# pisniffer.net
KiCad netlist of a schematic drawn in EAGLE
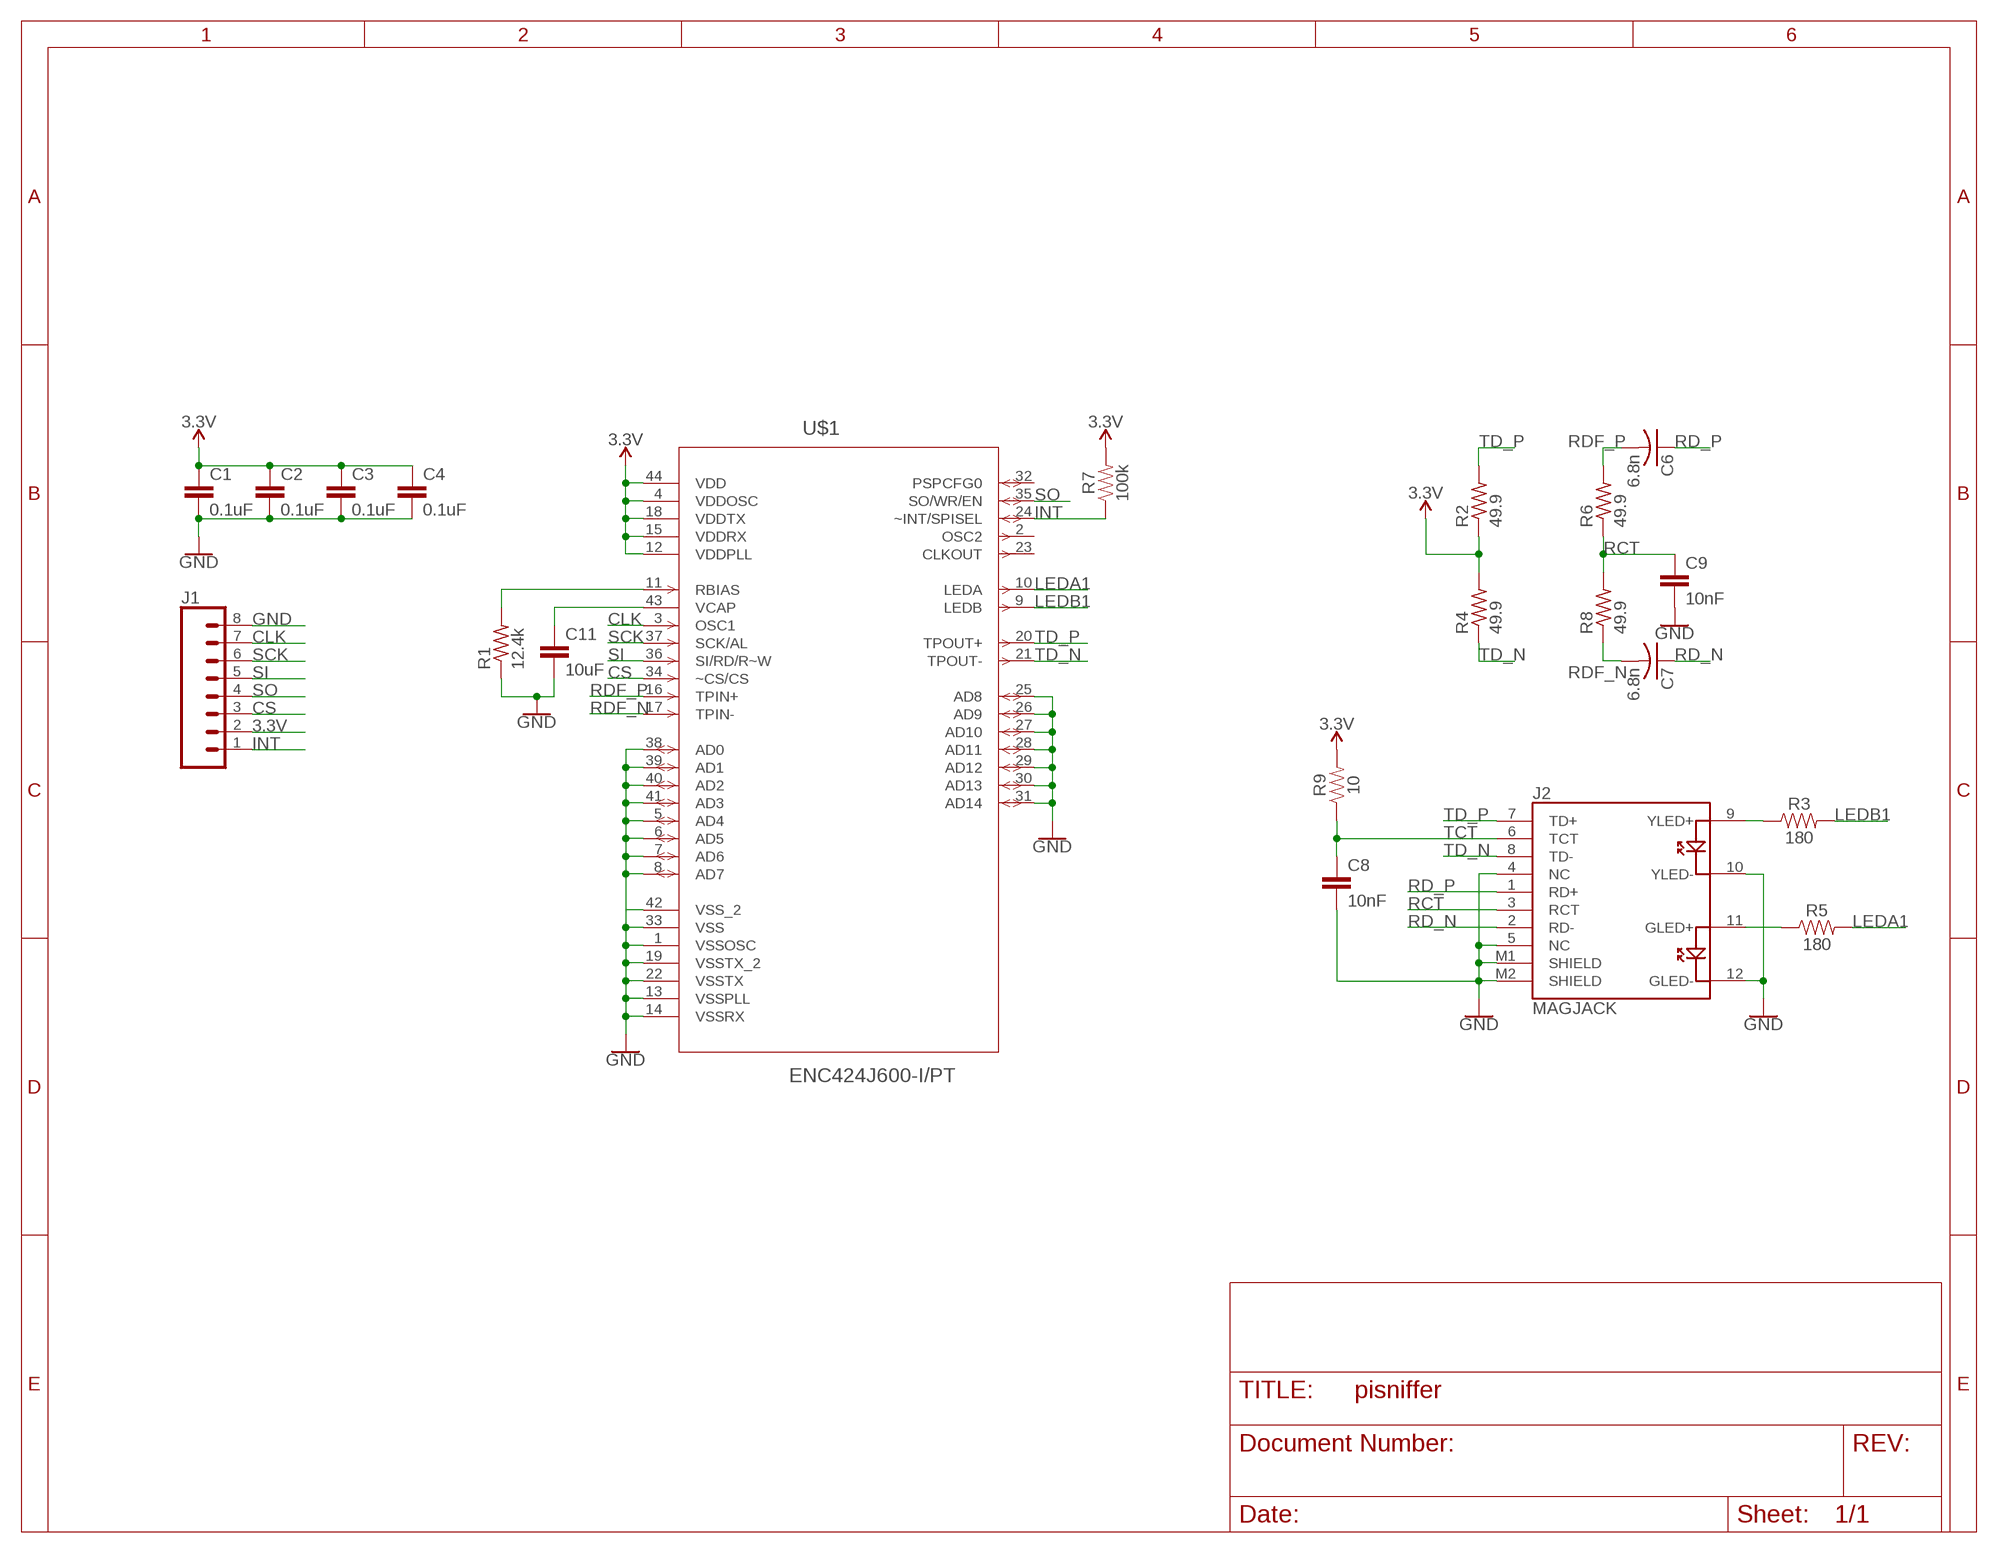
[diagram p0: schematic, sheet 1]

(export (version "E")
  (design (tool "Eeschema 10.0.6"))
  (components
    (comp (ref "C1")
      (value "0.1uF")
      (footprint "eagle-import:0603")
      (libsource (lib "eagle-import") (part "0.1UF-0603-25V-5%"))
    )
    (comp (ref "C2")
      (value "0.1uF")
      (footprint "eagle-import:0603")
      (libsource (lib "eagle-import") (part "0.1UF-0603-25V-5%"))
    )
    (comp (ref "C3")
      (value "0.1uF")
      (footprint "eagle-import:0603")
      (libsource (lib "eagle-import") (part "0.1UF-0603-25V-5%"))
    )
    (comp (ref "C4")
      (value "0.1uF")
      (footprint "eagle-import:0603")
      (libsource (lib "eagle-import") (part "0.1UF-0603-25V-5%"))
    )
    (comp (ref "C6")
      (value "6.8n")
      (footprint "eagle-import:C0603")
      (libsource (lib "eagle-import") (part "C-USC0603"))
    )
    (comp (ref "C7")
      (value "6.8n")
      (footprint "eagle-import:C0603")
      (libsource (lib "eagle-import") (part "C-USC0603"))
    )
    (comp (ref "C8")
      (value "10nF")
      (footprint "eagle-import:0603")
      (libsource (lib "eagle-import") (part "10NF-0603-50V-10%"))
    )
    (comp (ref "C9")
      (value "10nF")
      (footprint "eagle-import:0603")
      (libsource (lib "eagle-import") (part "10NF-0603-50V-10%"))
    )
    (comp (ref "C11")
      (value "10uF")
      (footprint "eagle-import:0603")
      (libsource (lib "eagle-import") (part "10UF-0603-6.3V-20%"))
    )
    (comp (ref "J1")
      (value "CONN_08\"")
      (footprint "eagle-import:1X08")
      (libsource (lib "eagle-import") (part "CONN_08{dblquote}"))
    )
    (comp (ref "J2")
      (value "MAGJACK")
      (footprint "eagle-import:MAGJACK")
      (libsource (lib "eagle-import") (part "MAGJACK"))
    )
    (comp (ref "R1")
      (value "12.4k")
      (footprint "eagle-import:R0603")
      (libsource (lib "eagle-import") (part "R-US_R0603"))
    )
    (comp (ref "R2")
      (value "49.9")
      (footprint "eagle-import:R0603")
      (libsource (lib "eagle-import") (part "R-US_R0603"))
    )
    (comp (ref "R3")
      (value "180")
      (footprint "eagle-import:0603")
      (libsource (lib "eagle-import") (part "180OHM-0603-1/10W-1%"))
    )
    (comp (ref "R4")
      (value "49.9")
      (footprint "eagle-import:R0603")
      (libsource (lib "eagle-import") (part "R-US_R0603"))
    )
    (comp (ref "R5")
      (value "180")
      (footprint "eagle-import:0603")
      (libsource (lib "eagle-import") (part "180OHM-0603-1/10W-1%"))
    )
    (comp (ref "R6")
      (value "49.9")
      (footprint "eagle-import:R0603")
      (libsource (lib "eagle-import") (part "R-US_R0603"))
    )
    (comp (ref "R7")
      (value "100k")
      (footprint "eagle-import:0603")
      (libsource (lib "eagle-import") (part "100KOHM-0603-1/10W-1%"))
    )
    (comp (ref "R8")
      (value "49.9")
      (footprint "eagle-import:R0603")
      (libsource (lib "eagle-import") (part "R-US_R0603"))
    )
    (comp (ref "R9")
      (value "10")
      (footprint "eagle-import:0603")
      (libsource (lib "eagle-import") (part "10OHM-0603-1/10W-1%"))
    )
    (comp (ref "U$1")
      (value "ENC424J600-I/PT")
      (footprint "eagle-import:QFP50P1200X1200X120-44N")
      (fields (field (name "MPN") "enc424j600-I/pt"))
      (libsource (lib "eagle-import") (part "ENC424J600-I/PT"))
    )
  )
  (nets
    (net (code "1") (name "/CLK") (class "Default")
      (node (ref "J1") (pin "7") (pinfunction "7_7") (pintype "passive"))
      (node (ref "U$1") (pin "3") (pinfunction "OSC1_3") (pintype "input"))
    )
    (net (code "2") (name "/CS") (class "Default")
      (node (ref "J1") (pin "3") (pinfunction "3_3") (pintype "passive"))
      (node (ref "U$1") (pin "34") (pinfunction "~{CS/CS}_34") (pintype "input"))
    )
    (net (code "3") (name "/INT") (class "Default")
      (node (ref "J1") (pin "1") (pinfunction "1_1") (pintype "passive"))
      (node (ref "R7") (pin "1") (pinfunction "1_1") (pintype "passive"))
      (node (ref "U$1") (pin "24") (pinfunction "~{INT/SPISEL}_24") (pintype "bidirectional"))
    )
    (net (code "4") (name "/LEDA1") (class "Default")
      (node (ref "R5") (pin "2") (pinfunction "2_2") (pintype "passive"))
      (node (ref "U$1") (pin "10") (pinfunction "LEDA_10") (pintype "output"))
    )
    (net (code "5") (name "/LEDB1") (class "Default")
      (node (ref "R3") (pin "2") (pinfunction "2_2") (pintype "passive"))
      (node (ref "U$1") (pin "9") (pinfunction "LEDB_9") (pintype "output"))
    )
    (net (code "6") (name "/RCT") (class "Default")
      (node (ref "C9") (pin "1") (pinfunction "1_1") (pintype "passive"))
      (node (ref "J2") (pin "3") (pinfunction "RCT_3") (pintype "bidirectional"))
      (node (ref "R6") (pin "1") (pinfunction "1_1") (pintype "passive"))
      (node (ref "R8") (pin "2") (pinfunction "2_2") (pintype "passive"))
    )
    (net (code "7") (name "/RDF_N") (class "Default")
      (node (ref "C7") (pin "2") (pinfunction "2_2") (pintype "passive"))
      (node (ref "R8") (pin "1") (pinfunction "1_1") (pintype "passive"))
      (node (ref "U$1") (pin "17") (pinfunction "TPIN-_17") (pintype "input"))
    )
    (net (code "8") (name "/RDF_P") (class "Default")
      (node (ref "C6") (pin "2") (pinfunction "2_2") (pintype "passive"))
      (node (ref "R6") (pin "2") (pinfunction "2_2") (pintype "passive"))
      (node (ref "U$1") (pin "16") (pinfunction "TPIN+_16") (pintype "input"))
    )
    (net (code "9") (name "/RD_N") (class "Default")
      (node (ref "C7") (pin "1") (pinfunction "1_1") (pintype "passive"))
      (node (ref "J2") (pin "2") (pinfunction "RD-_2") (pintype "bidirectional"))
    )
    (net (code "10") (name "/RD_P") (class "Default")
      (node (ref "C6") (pin "1") (pinfunction "1_1") (pintype "passive"))
      (node (ref "J2") (pin "1") (pinfunction "RD+_1") (pintype "bidirectional"))
    )
    (net (code "11") (name "/SCK") (class "Default")
      (node (ref "J1") (pin "6") (pinfunction "6_6") (pintype "passive"))
      (node (ref "U$1") (pin "37") (pinfunction "SCK/AL_37") (pintype "input"))
    )
    (net (code "12") (name "/SI") (class "Default")
      (node (ref "J1") (pin "5") (pinfunction "5_5") (pintype "passive"))
      (node (ref "U$1") (pin "36") (pinfunction "SI/RD/R~{W}_36") (pintype "input"))
    )
    (net (code "13") (name "/SO") (class "Default")
      (node (ref "J1") (pin "4") (pinfunction "4_4") (pintype "passive"))
      (node (ref "U$1") (pin "35") (pinfunction "SO/WR/EN_35") (pintype "bidirectional"))
    )
    (net (code "14") (name "/TCT") (class "Default")
      (node (ref "C8") (pin "1") (pinfunction "1_1") (pintype "passive"))
      (node (ref "J2") (pin "6") (pinfunction "TCT_6") (pintype "bidirectional"))
      (node (ref "R9") (pin "1") (pinfunction "1_1") (pintype "passive"))
    )
    (net (code "15") (name "/TD_N") (class "Default")
      (node (ref "J2") (pin "8") (pinfunction "TD-_8") (pintype "bidirectional"))
      (node (ref "R4") (pin "1") (pinfunction "1_1") (pintype "passive"))
      (node (ref "U$1") (pin "21") (pinfunction "TPOUT-_21") (pintype "output"))
    )
    (net (code "16") (name "/TD_P") (class "Default")
      (node (ref "J2") (pin "7") (pinfunction "TD+_7") (pintype "bidirectional"))
      (node (ref "R2") (pin "2") (pinfunction "2_2") (pintype "passive"))
      (node (ref "U$1") (pin "20") (pinfunction "TPOUT+_20") (pintype "output"))
    )
    (net (code "17") (name "3.3V") (class "Default")
      (node (ref "C1") (pin "1") (pinfunction "1_1") (pintype "passive"))
      (node (ref "C2") (pin "1") (pinfunction "1_1") (pintype "passive"))
      (node (ref "C3") (pin "1") (pinfunction "1_1") (pintype "passive"))
      (node (ref "C4") (pin "1") (pinfunction "1_1") (pintype "passive"))
      (node (ref "J1") (pin "2") (pinfunction "2_2") (pintype "passive"))
      (node (ref "R2") (pin "1") (pinfunction "1_1") (pintype "passive"))
      (node (ref "R4") (pin "2") (pinfunction "2_2") (pintype "passive"))
      (node (ref "R7") (pin "2") (pinfunction "2_2") (pintype "passive"))
      (node (ref "R9") (pin "2") (pinfunction "2_2") (pintype "passive"))
      (node (ref "U$1") (pin "12") (pinfunction "VDDPLL_12") (pintype "power_in"))
      (node (ref "U$1") (pin "15") (pinfunction "VDDRX_15") (pintype "power_in"))
      (node (ref "U$1") (pin "18") (pinfunction "VDDTX_18") (pintype "power_in"))
      (node (ref "U$1") (pin "4") (pinfunction "VDDOSC_4") (pintype "power_in"))
      (node (ref "U$1") (pin "44") (pinfunction "VDD_44") (pintype "power_in"))
    )
    (net (code "18") (name "GND") (class "Default")
      (node (ref "C1") (pin "2") (pinfunction "2_2") (pintype "passive"))
      (node (ref "C11") (pin "2") (pinfunction "2_2") (pintype "passive"))
      (node (ref "C2") (pin "2") (pinfunction "2_2") (pintype "passive"))
      (node (ref "C3") (pin "2") (pinfunction "2_2") (pintype "passive"))
      (node (ref "C4") (pin "2") (pinfunction "2_2") (pintype "passive"))
      (node (ref "C8") (pin "2") (pinfunction "2_2") (pintype "passive"))
      (node (ref "C9") (pin "2") (pinfunction "2_2") (pintype "passive"))
      (node (ref "J1") (pin "8") (pinfunction "8_8") (pintype "passive"))
      (node (ref "J2") (pin "10") (pinfunction "YLED-_10") (pintype "bidirectional"))
      (node (ref "J2") (pin "12") (pinfunction "GLED-_12") (pintype "bidirectional"))
      (node (ref "J2") (pin "4") (pinfunction "NC_4") (pintype "bidirectional"))
      (node (ref "J2") (pin "5") (pinfunction "NC_5") (pintype "bidirectional"))
      (node (ref "J2") (pin "M1") (pinfunction "SHIELD_M1") (pintype "bidirectional"))
      (node (ref "J2") (pin "M2") (pinfunction "SHIELD_M2") (pintype "bidirectional"))
      (node (ref "R1") (pin "1") (pinfunction "1_1") (pintype "passive"))
      (node (ref "U$1") (pin "1") (pinfunction "VSSOSC_1") (pintype "power_in"))
      (node (ref "U$1") (pin "13") (pinfunction "VSSPLL_13") (pintype "power_in"))
      (node (ref "U$1") (pin "14") (pinfunction "VSSRX_14") (pintype "power_in"))
      (node (ref "U$1") (pin "19") (pinfunction "VSSTX_2_19") (pintype "power_in"))
      (node (ref "U$1") (pin "22") (pinfunction "VSSTX_22") (pintype "power_in"))
      (node (ref "U$1") (pin "25") (pinfunction "AD8_25") (pintype "bidirectional"))
      (node (ref "U$1") (pin "26") (pinfunction "AD9_26") (pintype "bidirectional"))
      (node (ref "U$1") (pin "27") (pinfunction "AD10_27") (pintype "bidirectional"))
      (node (ref "U$1") (pin "28") (pinfunction "AD11_28") (pintype "bidirectional"))
      (node (ref "U$1") (pin "29") (pinfunction "AD12_29") (pintype "bidirectional"))
      (node (ref "U$1") (pin "30") (pinfunction "AD13_30") (pintype "bidirectional"))
      (node (ref "U$1") (pin "31") (pinfunction "AD14_31") (pintype "bidirectional"))
      (node (ref "U$1") (pin "33") (pinfunction "VSS_33") (pintype "power_in"))
      (node (ref "U$1") (pin "38") (pinfunction "AD0_38") (pintype "bidirectional"))
      (node (ref "U$1") (pin "39") (pinfunction "AD1_39") (pintype "bidirectional"))
      (node (ref "U$1") (pin "40") (pinfunction "AD2_40") (pintype "bidirectional"))
      (node (ref "U$1") (pin "41") (pinfunction "AD3_41") (pintype "bidirectional"))
      (node (ref "U$1") (pin "42") (pinfunction "VSS_2_42") (pintype "power_in"))
      (node (ref "U$1") (pin "5") (pinfunction "AD4_5") (pintype "bidirectional"))
      (node (ref "U$1") (pin "6") (pinfunction "AD5_6") (pintype "bidirectional"))
      (node (ref "U$1") (pin "7") (pinfunction "AD6_7") (pintype "bidirectional"))
      (node (ref "U$1") (pin "8") (pinfunction "AD7_8") (pintype "bidirectional"))
    )
    (net (code "19") (name "Net-(J2-GLED+)") (class "Default")
      (node (ref "J2") (pin "11") (pinfunction "GLED+_11") (pintype "bidirectional"))
      (node (ref "R5") (pin "1") (pinfunction "1_1") (pintype "passive"))
    )
    (net (code "20") (name "Net-(J2-YLED+)") (class "Default")
      (node (ref "J2") (pin "9") (pinfunction "YLED+_9") (pintype "bidirectional"))
      (node (ref "R3") (pin "1") (pinfunction "1_1") (pintype "passive"))
    )
    (net (code "21") (name "Net-(U$1-RBIAS)") (class "Default")
      (node (ref "R1") (pin "2") (pinfunction "2_2") (pintype "passive"))
      (node (ref "U$1") (pin "11") (pinfunction "RBIAS_11") (pintype "input"))
    )
    (net (code "22") (name "Net-(U$1-VCAP)") (class "Default")
      (node (ref "C11") (pin "1") (pinfunction "1_1") (pintype "passive"))
      (node (ref "U$1") (pin "43") (pinfunction "VCAP_43") (pintype "power_in"))
    )
    (net (code "23") (name "unconnected-(U$1-CLKOUT-Pad23)") (class "Default")
      (node (ref "U$1") (pin "23") (pinfunction "CLKOUT_23") (pintype "output"))
    )
    (net (code "24") (name "unconnected-(U$1-OSC2-Pad2)") (class "Default")
      (node (ref "U$1") (pin "2") (pinfunction "OSC2_2") (pintype "output"))
    )
    (net (code "25") (name "unconnected-(U$1-PSPCFG0-Pad32)") (class "Default")
      (node (ref "U$1") (pin "32") (pinfunction "PSPCFG0_32") (pintype "output"))
    )
  )
)
